# Esp-Nextion.net
KiCad netlist of a schematic drawn in Altium Designer
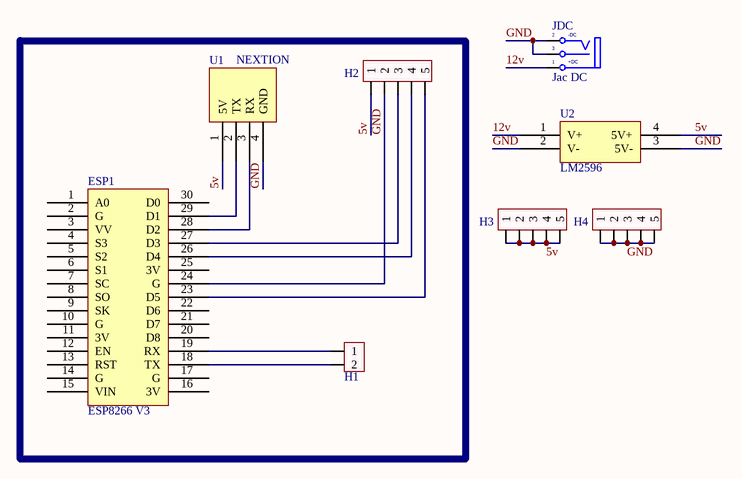
[diagram p0: Esp-Nextion.SchDoc]

(export (version "E")
  (design (tool "Eeschema 10.0.6"))
  (components
    (comp (ref "ESP1")
      (value "ESP8266 V3")
      (footprint "ESP8266 V3")
      (description "ESP8266")
      (libsource (lib "THU_VIEN_PQB_Schlib1") (part "ESP8266 V3"))
    )
    (comp (ref "H1")
      (value "Header2")
      (footprint "HDR2")
      (description "Header IDC, 2 x 1 Pin Vertical 2.54mm Pitch (Non-Boxed, Male)")
      (libsource (lib "LIBRARY") (part "Header2"))
    )
    (comp (ref "H2")
      (value "Header5")
      (footprint "Header5")
      (description "Header IDC, 5 x 1 Pin Vertical 2.54mm Pitch (Non-Boxed, Male)")
      (libsource (lib "LIBRARY") (part "Header5"))
    )
    (comp (ref "H3")
      (value "Header5")
      (footprint "Header5")
      (description "Header IDC, 5 x 1 Pin Vertical 2.54mm Pitch (Non-Boxed, Male)")
      (libsource (lib "LIBRARY") (part "Header5"))
    )
    (comp (ref "H4")
      (value "Header5")
      (footprint "Header5")
      (description "Header IDC, 5 x 1 Pin Vertical 2.54mm Pitch (Non-Boxed, Male)")
      (libsource (lib "LIBRARY") (part "Header5"))
    )
    (comp (ref "JDC")
      (value "Jac DC")
      (footprint "DC-IN")
      (description "Jac DC input")
      (libsource (lib "syhaunguyen") (part "DCIN"))
    )
    (comp (ref "U1")
      (value "NEXTION")
      (footprint "NEXTION")
      (libsource (lib "THU_VIEN_PQB_Schlib1") (part "NEXTION"))
    )
    (comp (ref "U2")
      (value "LM2596")
      (footprint "LM2596")
      (libsource (lib "THU_VIEN_PQB_Schlib1") (part "LM2596"))
    )
  )
  (nets
    (net (code "1") (name "/5v") (class "Default")
      (node (ref "H2") (pin "1") (pinfunction "1_1") (pintype "passive"))
      (node (ref "H3") (pin "1") (pinfunction "1_1") (pintype "passive"))
      (node (ref "H3") (pin "2") (pinfunction "2_2") (pintype "passive"))
      (node (ref "H3") (pin "3") (pinfunction "3_3") (pintype "passive"))
      (node (ref "H3") (pin "4") (pinfunction "4_4") (pintype "passive"))
      (node (ref "H3") (pin "5") (pinfunction "5_5") (pintype "passive"))
      (node (ref "U1") (pin "1") (pinfunction "5V_1") (pintype "power_in"))
      (node (ref "U2") (pin "4") (pinfunction "5V+_4") (pintype "power_in"))
    )
    (net (code "2") (name "/12v") (class "Default")
      (node (ref "JDC") (pin "1") (pinfunction "T_1") (pintype "passive"))
      (node (ref "U2") (pin "1") (pinfunction "V+_1") (pintype "power_in"))
    )
    (net (code "3") (name "/GND") (class "Default")
      (node (ref "ESP1") (pin "24") (pinfunction "G_24") (pintype "power_in"))
      (node (ref "H2") (pin "2") (pinfunction "2_2") (pintype "passive"))
      (node (ref "H4") (pin "1") (pinfunction "1_1") (pintype "passive"))
      (node (ref "H4") (pin "2") (pinfunction "2_2") (pintype "passive"))
      (node (ref "H4") (pin "3") (pinfunction "3_3") (pintype "passive"))
      (node (ref "H4") (pin "4") (pinfunction "4_4") (pintype "passive"))
      (node (ref "H4") (pin "5") (pinfunction "5_5") (pintype "passive"))
      (node (ref "JDC") (pin "2") (pinfunction "TN_2") (pintype "passive"))
      (node (ref "JDC") (pin "3") (pinfunction "S_3") (pintype "power_in"))
      (node (ref "U1") (pin "4") (pinfunction "GND_4") (pintype "power_in"))
      (node (ref "U2") (pin "2") (pinfunction "V-_2") (pintype "power_in"))
      (node (ref "U2") (pin "3") (pinfunction "5V-_3") (pintype "power_in"))
    )
    (net (code "4") (name "Net-(ESP1-D1)") (class "Default")
      (node (ref "ESP1") (pin "29") (pinfunction "D1_29") (pintype "passive"))
      (node (ref "U1") (pin "2") (pinfunction "TX_2") (pintype "passive"))
    )
    (net (code "5") (name "Net-(ESP1-D2)") (class "Default")
      (node (ref "ESP1") (pin "28") (pinfunction "D2_28") (pintype "passive"))
      (node (ref "U1") (pin "3") (pinfunction "RX_3") (pintype "passive"))
    )
    (net (code "6") (name "Net-(ESP1-D3)") (class "Default")
      (node (ref "ESP1") (pin "27") (pinfunction "D3_27") (pintype "passive"))
      (node (ref "H2") (pin "3") (pinfunction "3_3") (pintype "passive"))
    )
    (net (code "7") (name "Net-(ESP1-D4)") (class "Default")
      (node (ref "ESP1") (pin "26") (pinfunction "D4_26") (pintype "passive"))
      (node (ref "H2") (pin "4") (pinfunction "4_4") (pintype "passive"))
    )
    (net (code "8") (name "Net-(ESP1-D5)") (class "Default")
      (node (ref "ESP1") (pin "23") (pinfunction "D5_23") (pintype "passive"))
      (node (ref "H2") (pin "5") (pinfunction "5_5") (pintype "passive"))
    )
    (net (code "9") (name "Net-(ESP1-RX)") (class "Default")
      (node (ref "ESP1") (pin "19") (pinfunction "RX_19") (pintype "passive"))
      (node (ref "H1") (pin "1") (pinfunction "1_1") (pintype "passive"))
    )
    (net (code "10") (name "Net-(ESP1-TX)") (class "Default")
      (node (ref "ESP1") (pin "18") (pinfunction "TX_18") (pintype "passive"))
      (node (ref "H1") (pin "2") (pinfunction "2_2") (pintype "passive"))
    )
    (net (code "11") (name "unconnected-(ESP1-3V-Pad11)") (class "Default")
      (node (ref "ESP1") (pin "11") (pinfunction "3V_11") (pintype "power_in"))
    )
    (net (code "12") (name "unconnected-(ESP1-3V-Pad16)") (class "Default")
      (node (ref "ESP1") (pin "16") (pinfunction "3V_16") (pintype "power_in"))
    )
    (net (code "13") (name "unconnected-(ESP1-3V-Pad25)") (class "Default")
      (node (ref "ESP1") (pin "25") (pinfunction "3V_25") (pintype "power_in"))
    )
    (net (code "14") (name "unconnected-(ESP1-A0-Pad1)") (class "Default")
      (node (ref "ESP1") (pin "1") (pinfunction "A0_1") (pintype "passive"))
    )
    (net (code "15") (name "unconnected-(ESP1-D0-Pad30)") (class "Default")
      (node (ref "ESP1") (pin "30") (pinfunction "D0_30") (pintype "passive"))
    )
    (net (code "16") (name "unconnected-(ESP1-D6-Pad22)") (class "Default")
      (node (ref "ESP1") (pin "22") (pinfunction "D6_22") (pintype "passive"))
    )
    (net (code "17") (name "unconnected-(ESP1-D7-Pad21)") (class "Default")
      (node (ref "ESP1") (pin "21") (pinfunction "D7_21") (pintype "passive"))
    )
    (net (code "18") (name "unconnected-(ESP1-D8-Pad20)") (class "Default")
      (node (ref "ESP1") (pin "20") (pinfunction "D8_20") (pintype "passive"))
    )
    (net (code "19") (name "unconnected-(ESP1-EN-Pad12)") (class "Default")
      (node (ref "ESP1") (pin "12") (pinfunction "EN_12") (pintype "passive"))
    )
    (net (code "20") (name "unconnected-(ESP1-G-Pad2)") (class "Default")
      (node (ref "ESP1") (pin "2") (pinfunction "G_2") (pintype "power_in"))
    )
    (net (code "21") (name "unconnected-(ESP1-G-Pad10)") (class "Default")
      (node (ref "ESP1") (pin "10") (pinfunction "G_10") (pintype "power_in"))
    )
    (net (code "22") (name "unconnected-(ESP1-G-Pad14)") (class "Default")
      (node (ref "ESP1") (pin "14") (pinfunction "G_14") (pintype "power_in"))
    )
    (net (code "23") (name "unconnected-(ESP1-G-Pad17)") (class "Default")
      (node (ref "ESP1") (pin "17") (pinfunction "G_17") (pintype "power_in"))
    )
    (net (code "24") (name "unconnected-(ESP1-RST-Pad13)") (class "Default")
      (node (ref "ESP1") (pin "13") (pinfunction "RST_13") (pintype "passive"))
    )
    (net (code "25") (name "unconnected-(ESP1-S1-Pad6)") (class "Default")
      (node (ref "ESP1") (pin "6") (pinfunction "S1_6") (pintype "passive"))
    )
    (net (code "26") (name "unconnected-(ESP1-S2-Pad5)") (class "Default")
      (node (ref "ESP1") (pin "5") (pinfunction "S2_5") (pintype "passive"))
    )
    (net (code "27") (name "unconnected-(ESP1-S3-Pad4)") (class "Default")
      (node (ref "ESP1") (pin "4") (pinfunction "S3_4") (pintype "passive"))
    )
    (net (code "28") (name "unconnected-(ESP1-SC-Pad7)") (class "Default")
      (node (ref "ESP1") (pin "7") (pinfunction "SC_7") (pintype "passive"))
    )
    (net (code "29") (name "unconnected-(ESP1-SK-Pad9)") (class "Default")
      (node (ref "ESP1") (pin "9") (pinfunction "SK_9") (pintype "passive"))
    )
    (net (code "30") (name "unconnected-(ESP1-SO-Pad8)") (class "Default")
      (node (ref "ESP1") (pin "8") (pinfunction "SO_8") (pintype "passive"))
    )
    (net (code "31") (name "unconnected-(ESP1-VIN-Pad15)") (class "Default")
      (node (ref "ESP1") (pin "15") (pinfunction "VIN_15") (pintype "power_in"))
    )
    (net (code "32") (name "unconnected-(ESP1-VV-Pad3)") (class "Default")
      (node (ref "ESP1") (pin "3") (pinfunction "VV_3") (pintype "passive"))
    )
  )
)
